# Sheet_Top_Front.net
KiCad netlist of a schematic drawn in Altium Designer
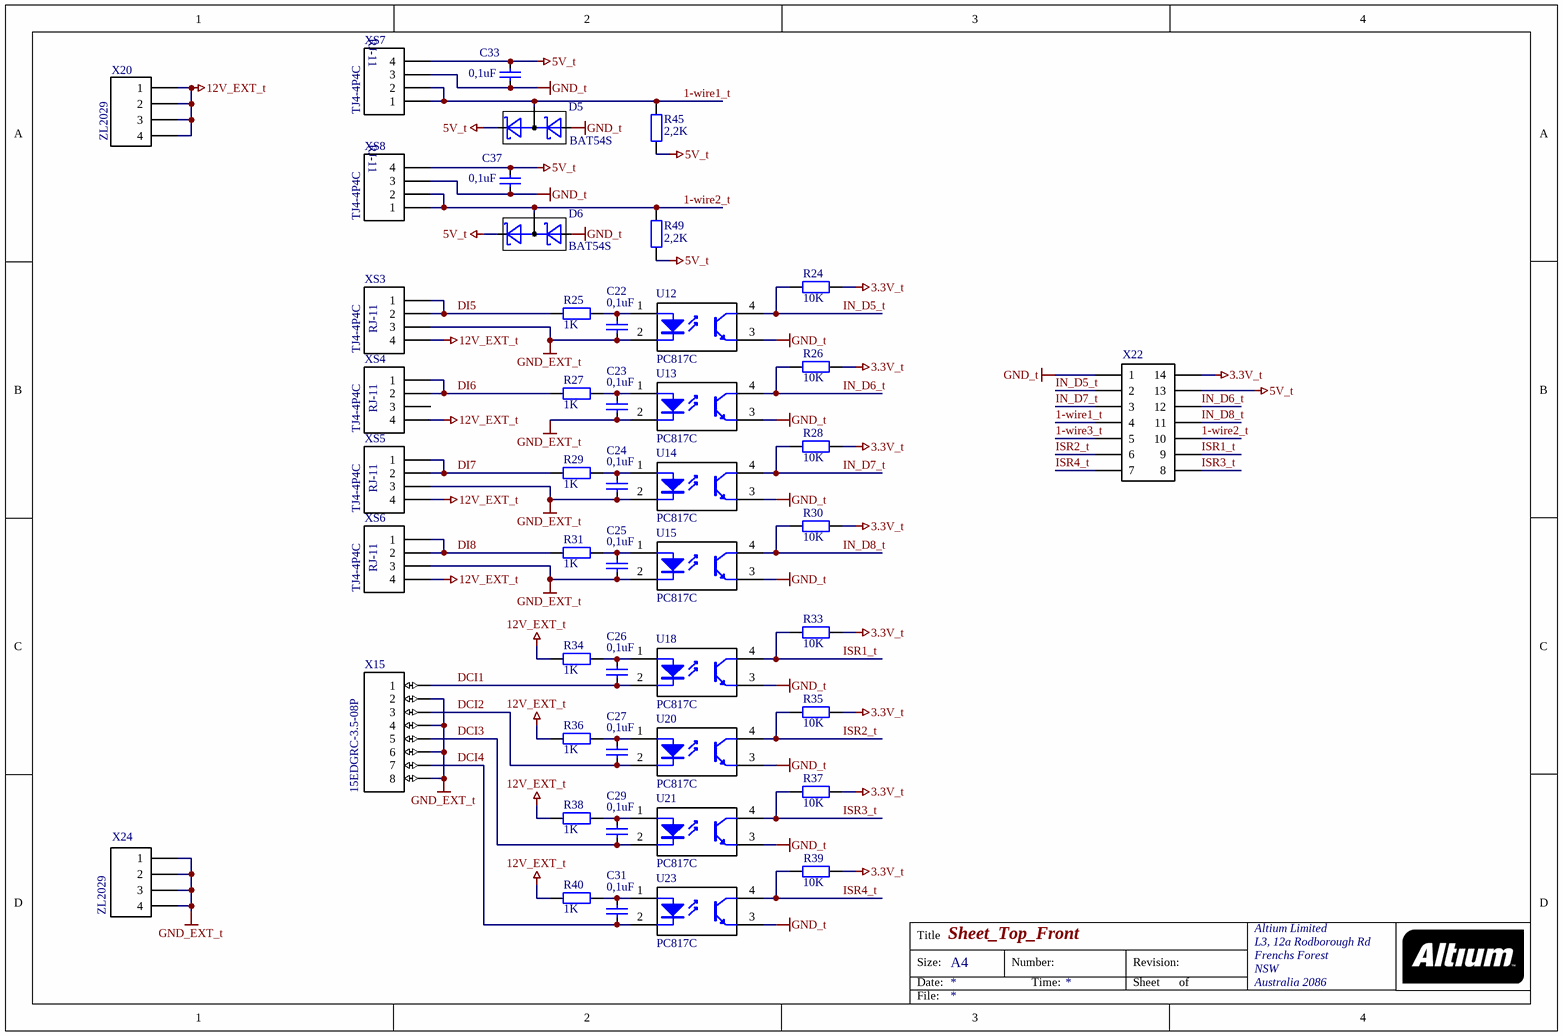
[diagram p0: Sheet_Top_Front.SchDoc]

(export (version "E")
  (design (tool "Eeschema 10.0.6"))
  (components
    (comp (ref "C22")
      (value "0,1uF")
      (footprint "C_0805")
      (description "Capacitor semi")
      (fields (field (name "Comment") "Cap_Semi"))
      (libsource (lib "Capacitor") (part "Cap_Semi"))
    )
    (comp (ref "C23")
      (value "0,1uF")
      (footprint "C_0805")
      (description "Capacitor semi")
      (fields (field (name "Comment") "Cap_Semi"))
      (libsource (lib "Capacitor") (part "Cap_Semi"))
    )
    (comp (ref "C24")
      (value "0,1uF")
      (footprint "C_0805")
      (description "Capacitor semi")
      (fields (field (name "Comment") "Cap_Semi"))
      (libsource (lib "Capacitor") (part "Cap_Semi"))
    )
    (comp (ref "C25")
      (value "0,1uF")
      (footprint "C_0805")
      (description "Capacitor semi")
      (fields (field (name "Comment") "Cap_Semi"))
      (libsource (lib "Capacitor") (part "Cap_Semi"))
    )
    (comp (ref "C26")
      (value "0,1uF")
      (footprint "C_0805")
      (description "Capacitor semi")
      (fields (field (name "Comment") "Cap_Semi"))
      (libsource (lib "Capacitor") (part "Cap_Semi"))
    )
    (comp (ref "C27")
      (value "0,1uF")
      (footprint "C_0805")
      (description "Capacitor semi")
      (fields (field (name "Comment") "Cap_Semi"))
      (libsource (lib "Capacitor") (part "Cap_Semi"))
    )
    (comp (ref "C29")
      (value "0,1uF")
      (footprint "C_0805")
      (description "Capacitor semi")
      (fields (field (name "Comment") "Cap_Semi"))
      (libsource (lib "Capacitor") (part "Cap_Semi"))
    )
    (comp (ref "C31")
      (value "0,1uF")
      (footprint "C_0805")
      (description "Capacitor semi")
      (fields (field (name "Comment") "Cap_Semi"))
      (libsource (lib "Capacitor") (part "Cap_Semi"))
    )
    (comp (ref "C33")
      (value "0,1uF")
      (footprint "C_0805")
      (description "Capacitor semi")
      (fields (field (name "Comment") "Cap_Semi"))
      (libsource (lib "Capacitor") (part "Cap_Semi"))
    )
    (comp (ref "C37")
      (value "0,1uF")
      (footprint "C_0805")
      (description "Capacitor semi")
      (fields (field (name "Comment") "Cap_Semi"))
      (libsource (lib "Capacitor") (part "Cap_Semi"))
    )
    (comp (ref "D5")
      (value "BAT54S")
      (footprint "SOT-23_d")
      (description "Diode Schottky")
      (libsource (lib "Diode") (part "BAT54S"))
    )
    (comp (ref "D6")
      (value "BAT54S")
      (footprint "SOT-23_d")
      (description "Diode Schottky")
      (libsource (lib "Diode") (part "BAT54S"))
    )
    (comp (ref "R24")
      (value "10K")
      (footprint "R_0805")
      (description "Resistor")
      (libsource (lib "Resistors") (part "Resistor"))
    )
    (comp (ref "R25")
      (value "1K")
      (footprint "R_0805")
      (description "Resistor")
      (libsource (lib "Resistors") (part "Resistor"))
    )
    (comp (ref "R26")
      (value "10K")
      (footprint "R_0805")
      (description "Resistor")
      (libsource (lib "Resistors") (part "Resistor"))
    )
    (comp (ref "R27")
      (value "1K")
      (footprint "R_0805")
      (description "Resistor")
      (libsource (lib "Resistors") (part "Resistor"))
    )
    (comp (ref "R28")
      (value "10K")
      (footprint "R_0805")
      (description "Resistor")
      (libsource (lib "Resistors") (part "Resistor"))
    )
    (comp (ref "R29")
      (value "1K")
      (footprint "R_0805")
      (description "Resistor")
      (libsource (lib "Resistors") (part "Resistor"))
    )
    (comp (ref "R30")
      (value "10K")
      (footprint "R_0805")
      (description "Resistor")
      (libsource (lib "Resistors") (part "Resistor"))
    )
    (comp (ref "R31")
      (value "1K")
      (footprint "R_0805")
      (description "Resistor")
      (libsource (lib "Resistors") (part "Resistor"))
    )
    (comp (ref "R33")
      (value "10K")
      (footprint "R_0805")
      (description "Resistor")
      (libsource (lib "Resistors") (part "Resistor"))
    )
    (comp (ref "R34")
      (value "1K")
      (footprint "R_0805")
      (description "Resistor")
      (libsource (lib "Resistors") (part "Resistor"))
    )
    (comp (ref "R35")
      (value "10K")
      (footprint "R_0805")
      (description "Resistor")
      (libsource (lib "Resistors") (part "Resistor"))
    )
    (comp (ref "R36")
      (value "1K")
      (footprint "R_0805")
      (description "Resistor")
      (libsource (lib "Resistors") (part "Resistor"))
    )
    (comp (ref "R37")
      (value "10K")
      (footprint "R_0805")
      (description "Resistor")
      (libsource (lib "Resistors") (part "Resistor"))
    )
    (comp (ref "R38")
      (value "1K")
      (footprint "R_0805")
      (description "Resistor")
      (libsource (lib "Resistors") (part "Resistor"))
    )
    (comp (ref "R39")
      (value "10K")
      (footprint "R_0805")
      (description "Resistor")
      (libsource (lib "Resistors") (part "Resistor"))
    )
    (comp (ref "R40")
      (value "1K")
      (footprint "R_0805")
      (description "Resistor")
      (libsource (lib "Resistors") (part "Resistor"))
    )
    (comp (ref "R45")
      (value "2,2K")
      (footprint "R_0805")
      (description "Resistor")
      (libsource (lib "Resistors") (part "Resistor"))
    )
    (comp (ref "R49")
      (value "2,2K")
      (footprint "R_0805")
      (description "Resistor")
      (libsource (lib "Resistors") (part "Resistor"))
    )
    (comp (ref "U12")
      (value "PC817C")
      (footprint "DIP-4")
      (description "Optocoupler")
      (libsource (lib "Chip_Packaging") (part "PC817"))
    )
    (comp (ref "U13")
      (value "PC817C")
      (footprint "DIP-4")
      (description "Optocoupler")
      (libsource (lib "Chip_Packaging") (part "PC817"))
    )
    (comp (ref "U14")
      (value "PC817C")
      (footprint "DIP-4")
      (description "Optocoupler")
      (libsource (lib "Chip_Packaging") (part "PC817"))
    )
    (comp (ref "U15")
      (value "PC817C")
      (footprint "DIP-4")
      (description "Optocoupler")
      (libsource (lib "Chip_Packaging") (part "PC817"))
    )
    (comp (ref "U18")
      (value "PC817C")
      (footprint "DIP-4")
      (description "Optocoupler")
      (libsource (lib "Chip_Packaging") (part "PC817"))
    )
    (comp (ref "U20")
      (value "PC817C")
      (footprint "DIP-4")
      (description "Optocoupler")
      (libsource (lib "Chip_Packaging") (part "PC817"))
    )
    (comp (ref "U21")
      (value "PC817C")
      (footprint "DIP-4")
      (description "Optocoupler")
      (libsource (lib "Chip_Packaging") (part "PC817"))
    )
    (comp (ref "U23")
      (value "PC817C")
      (footprint "DIP-4")
      (description "Optocoupler")
      (libsource (lib "Chip_Packaging") (part "PC817"))
    )
    (comp (ref "X15")
      (value "15EDGRC-3.5-08P")
      (footprint "MC_3.5_8")
      (description "Connector 3.5mm")
      (libsource (lib "Connect") (part "MC_3.5_8"))
    )
    (comp (ref "X20")
      (value "ZL2029")
      (footprint "PLS-4-3D")
      (description "Header, 4-Pin")
      (fields (field (name "ALTIUM_UNNAMED_1") "ZL2029") (field (name "PUBLISHER") "Altium Limited"))
      (libsource (lib "Connect") (part "PLS-4"))
    )
    (comp (ref "X22")
      (value "PLS2-14")
      (footprint "PLS2-14")
      (description "Header, 14-Pin")
      (libsource (lib "Connect") (part "PLS2-14"))
    )
    (comp (ref "X24")
      (value "PLS-4")
      (footprint "PLS-4-3D")
      (description "ZL2029")
      (fields (field (name "ALTIUM_UNNAMED_1") "ZL2029") (field (name "PUBLISHER") "Altium Limited"))
      (libsource (lib "Connect") (part "PLS-4"))
    )
    (comp (ref "XS3")
      (value "RJ-11")
      (footprint "RJ-11 - TJ4-4P4C")
      (description "TJ4-4P4C")
      (fields (field (name "ALTIUM_UNNAMED_1") "TJ4-4P4C"))
      (libsource (lib "Connect") (part "RJ-11"))
    )
    (comp (ref "XS4")
      (value "RJ-11")
      (footprint "RJ-11 - TJ4-4P4C")
      (description "TJ4-4P4C")
      (fields (field (name "ALTIUM_UNNAMED_1") "TJ4-4P4C"))
      (libsource (lib "Connect") (part "RJ-11"))
    )
    (comp (ref "XS5")
      (value "RJ-11")
      (footprint "RJ-11 - TJ4-4P4C")
      (description "TJ4-4P4C")
      (fields (field (name "ALTIUM_UNNAMED_1") "TJ4-4P4C"))
      (libsource (lib "Connect") (part "RJ-11"))
    )
    (comp (ref "XS6")
      (value "RJ-11")
      (footprint "RJ-11 - TJ4-4P4C")
      (description "TJ4-4P4C")
      (fields (field (name "ALTIUM_UNNAMED_1") "TJ4-4P4C"))
      (libsource (lib "Connect") (part "RJ-11"))
    )
    (comp (ref "XS7")
      (value "RJ-11")
      (footprint "RJ-11 - TJ4-4P4C")
      (description "TJ4-4P4C")
      (fields (field (name "ALTIUM_UNNAMED_1") "TJ4-4P4C"))
      (libsource (lib "") (part "RJ-11_1"))
    )
    (comp (ref "XS8")
      (value "RJ-11")
      (footprint "RJ-11 - TJ4-4P4C")
      (description "TJ4-4P4C")
      (fields (field (name "ALTIUM_UNNAMED_1") "TJ4-4P4C"))
      (libsource (lib "") (part "RJ-11_1"))
    )
  )
  (nets
    (net (code "1") (name "/1-wire1_t") (class "Default")
      (node (ref "D5") (pin "3") (pinfunction "CA_3") (pintype "passive"))
      (node (ref "R45") (pin "1") (pinfunction "1_1") (pintype "passive"))
      (node (ref "X22") (pin "4") (pinfunction "4_4") (pintype "passive"))
      (node (ref "XS7") (pin "1") (pinfunction "1_1") (pintype "passive"))
      (node (ref "XS7") (pin "2") (pinfunction "2_2") (pintype "passive"))
    )
    (net (code "2") (name "/1-wire2_t") (class "Default")
      (node (ref "D6") (pin "3") (pinfunction "CA_3") (pintype "passive"))
      (node (ref "R49") (pin "1") (pinfunction "1_1") (pintype "passive"))
      (node (ref "X22") (pin "10") (pinfunction "10_10") (pintype "passive"))
      (node (ref "XS8") (pin "1") (pinfunction "1_1") (pintype "passive"))
      (node (ref "XS8") (pin "2") (pinfunction "2_2") (pintype "passive"))
    )
    (net (code "3") (name "/1-wire3_t") (class "Default")
      (node (ref "X22") (pin "5") (pinfunction "5_5") (pintype "passive"))
    )
    (net (code "4") (name "/DCI1") (class "Default")
      (node (ref "C26") (pin "2") (pinfunction "2_2") (pintype "passive"))
      (node (ref "U18") (pin "2") (pinfunction "K_2") (pintype "passive"))
      (node (ref "X15") (pin "1") (pinfunction "1_1") (pintype "bidirectional"))
    )
    (net (code "5") (name "/DCI2") (class "Default")
      (node (ref "C27") (pin "2") (pinfunction "2_2") (pintype "passive"))
      (node (ref "U20") (pin "2") (pinfunction "K_2") (pintype "passive"))
      (node (ref "X15") (pin "3") (pinfunction "3_3") (pintype "bidirectional"))
    )
    (net (code "6") (name "/DCI3") (class "Default")
      (node (ref "C29") (pin "2") (pinfunction "2_2") (pintype "passive"))
      (node (ref "U21") (pin "2") (pinfunction "K_2") (pintype "passive"))
      (node (ref "X15") (pin "5") (pinfunction "5_5") (pintype "bidirectional"))
    )
    (net (code "7") (name "/DCI4") (class "Default")
      (node (ref "C31") (pin "2") (pinfunction "2_2") (pintype "passive"))
      (node (ref "U23") (pin "2") (pinfunction "K_2") (pintype "passive"))
      (node (ref "X15") (pin "7") (pinfunction "7_7") (pintype "bidirectional"))
    )
    (net (code "8") (name "/DI5") (class "Default")
      (node (ref "R25") (pin "2") (pinfunction "2_2") (pintype "passive"))
      (node (ref "XS3") (pin "1") (pinfunction "1_1") (pintype "passive"))
      (node (ref "XS3") (pin "2") (pinfunction "2_2") (pintype "passive"))
    )
    (net (code "9") (name "/DI6") (class "Default")
      (node (ref "R27") (pin "2") (pinfunction "2_2") (pintype "passive"))
      (node (ref "XS4") (pin "1") (pinfunction "1_1") (pintype "passive"))
      (node (ref "XS4") (pin "2") (pinfunction "2_2") (pintype "passive"))
    )
    (net (code "10") (name "/DI7") (class "Default")
      (node (ref "R29") (pin "2") (pinfunction "2_2") (pintype "passive"))
      (node (ref "XS5") (pin "1") (pinfunction "1_1") (pintype "passive"))
      (node (ref "XS5") (pin "2") (pinfunction "2_2") (pintype "passive"))
    )
    (net (code "11") (name "/DI8") (class "Default")
      (node (ref "R31") (pin "2") (pinfunction "2_2") (pintype "passive"))
      (node (ref "XS6") (pin "1") (pinfunction "1_1") (pintype "passive"))
      (node (ref "XS6") (pin "2") (pinfunction "2_2") (pintype "passive"))
    )
    (net (code "12") (name "/IN_D5_t") (class "Default")
      (node (ref "R24") (pin "2") (pinfunction "2_2") (pintype "passive"))
      (node (ref "U12") (pin "4") (pinfunction "C_4") (pintype "passive"))
      (node (ref "X22") (pin "2") (pinfunction "2_2") (pintype "passive"))
    )
    (net (code "13") (name "/IN_D6_t") (class "Default")
      (node (ref "R26") (pin "2") (pinfunction "2_2") (pintype "passive"))
      (node (ref "U13") (pin "4") (pinfunction "C_4") (pintype "passive"))
      (node (ref "X22") (pin "12") (pinfunction "12_12") (pintype "passive"))
    )
    (net (code "14") (name "/IN_D7_t") (class "Default")
      (node (ref "R28") (pin "2") (pinfunction "2_2") (pintype "passive"))
      (node (ref "U14") (pin "4") (pinfunction "C_4") (pintype "passive"))
      (node (ref "X22") (pin "3") (pinfunction "3_3") (pintype "passive"))
    )
    (net (code "15") (name "/IN_D8_t") (class "Default")
      (node (ref "R30") (pin "2") (pinfunction "2_2") (pintype "passive"))
      (node (ref "U15") (pin "4") (pinfunction "C_4") (pintype "passive"))
      (node (ref "X22") (pin "11") (pinfunction "11_11") (pintype "passive"))
    )
    (net (code "16") (name "/ISR1_t") (class "Default")
      (node (ref "R33") (pin "2") (pinfunction "2_2") (pintype "passive"))
      (node (ref "U18") (pin "4") (pinfunction "C_4") (pintype "passive"))
      (node (ref "X22") (pin "9") (pinfunction "9_9") (pintype "passive"))
    )
    (net (code "17") (name "/ISR2_t") (class "Default")
      (node (ref "R35") (pin "2") (pinfunction "2_2") (pintype "passive"))
      (node (ref "U20") (pin "4") (pinfunction "C_4") (pintype "passive"))
      (node (ref "X22") (pin "6") (pinfunction "6_6") (pintype "passive"))
    )
    (net (code "18") (name "/ISR3_t") (class "Default")
      (node (ref "R37") (pin "2") (pinfunction "2_2") (pintype "passive"))
      (node (ref "U21") (pin "4") (pinfunction "C_4") (pintype "passive"))
      (node (ref "X22") (pin "8") (pinfunction "8_8") (pintype "passive"))
    )
    (net (code "19") (name "/ISR4_t") (class "Default")
      (node (ref "R39") (pin "2") (pinfunction "2_2") (pintype "passive"))
      (node (ref "U23") (pin "4") (pinfunction "C_4") (pintype "passive"))
      (node (ref "X22") (pin "7") (pinfunction "7_7") (pintype "passive"))
    )
    (net (code "20") (name "3.3V_t") (class "Default")
      (node (ref "R24") (pin "1") (pinfunction "1_1") (pintype "passive"))
      (node (ref "R26") (pin "1") (pinfunction "1_1") (pintype "passive"))
      (node (ref "R28") (pin "1") (pinfunction "1_1") (pintype "passive"))
      (node (ref "R30") (pin "1") (pinfunction "1_1") (pintype "passive"))
      (node (ref "R33") (pin "1") (pinfunction "1_1") (pintype "passive"))
      (node (ref "R35") (pin "1") (pinfunction "1_1") (pintype "passive"))
      (node (ref "R37") (pin "1") (pinfunction "1_1") (pintype "passive"))
      (node (ref "R39") (pin "1") (pinfunction "1_1") (pintype "passive"))
      (node (ref "X22") (pin "14") (pinfunction "14_14") (pintype "passive"))
    )
    (net (code "21") (name "5V_t") (class "Default")
      (node (ref "C33") (pin "1") (pinfunction "1_1") (pintype "passive"))
      (node (ref "C37") (pin "1") (pinfunction "1_1") (pintype "passive"))
      (node (ref "D5") (pin "2") (pinfunction "C_2") (pintype "passive"))
      (node (ref "D6") (pin "2") (pinfunction "C_2") (pintype "passive"))
      (node (ref "R45") (pin "2") (pinfunction "2_2") (pintype "passive"))
      (node (ref "R49") (pin "2") (pinfunction "2_2") (pintype "passive"))
      (node (ref "X22") (pin "13") (pinfunction "13_13") (pintype "passive"))
      (node (ref "XS7") (pin "4") (pinfunction "4_4") (pintype "passive"))
      (node (ref "XS8") (pin "4") (pinfunction "4_4") (pintype "passive"))
    )
    (net (code "22") (name "12V_EXT_t") (class "Default")
      (node (ref "R34") (pin "2") (pinfunction "2_2") (pintype "passive"))
      (node (ref "R36") (pin "2") (pinfunction "2_2") (pintype "passive"))
      (node (ref "R38") (pin "2") (pinfunction "2_2") (pintype "passive"))
      (node (ref "R40") (pin "2") (pinfunction "2_2") (pintype "passive"))
      (node (ref "X20") (pin "1") (pinfunction "1_1") (pintype "passive"))
      (node (ref "X20") (pin "2") (pinfunction "2_2") (pintype "passive"))
      (node (ref "X20") (pin "3") (pinfunction "3_3") (pintype "passive"))
      (node (ref "X20") (pin "4") (pinfunction "4_4") (pintype "passive"))
      (node (ref "XS3") (pin "4") (pinfunction "4_4") (pintype "passive"))
      (node (ref "XS4") (pin "4") (pinfunction "4_4") (pintype "passive"))
      (node (ref "XS5") (pin "4") (pinfunction "4_4") (pintype "passive"))
      (node (ref "XS6") (pin "4") (pinfunction "4_4") (pintype "passive"))
    )
    (net (code "23") (name "GND_EXT_t") (class "Default")
      (node (ref "C22") (pin "2") (pinfunction "2_2") (pintype "passive"))
      (node (ref "C23") (pin "2") (pinfunction "2_2") (pintype "passive"))
      (node (ref "C24") (pin "2") (pinfunction "2_2") (pintype "passive"))
      (node (ref "C25") (pin "2") (pinfunction "2_2") (pintype "passive"))
      (node (ref "U12") (pin "2") (pinfunction "K_2") (pintype "passive"))
      (node (ref "U13") (pin "2") (pinfunction "K_2") (pintype "passive"))
      (node (ref "U14") (pin "2") (pinfunction "K_2") (pintype "passive"))
      (node (ref "U15") (pin "2") (pinfunction "K_2") (pintype "passive"))
      (node (ref "X15") (pin "2") (pinfunction "2_2") (pintype "bidirectional"))
      (node (ref "X15") (pin "4") (pinfunction "4_4") (pintype "bidirectional"))
      (node (ref "X15") (pin "6") (pinfunction "6_6") (pintype "bidirectional"))
      (node (ref "X15") (pin "8") (pinfunction "8_8") (pintype "bidirectional"))
      (node (ref "X24") (pin "1") (pinfunction "1_1") (pintype "passive"))
      (node (ref "X24") (pin "2") (pinfunction "2_2") (pintype "passive"))
      (node (ref "X24") (pin "3") (pinfunction "3_3") (pintype "passive"))
      (node (ref "X24") (pin "4") (pinfunction "4_4") (pintype "passive"))
      (node (ref "XS3") (pin "3") (pinfunction "3_3") (pintype "passive"))
      (node (ref "XS5") (pin "3") (pinfunction "3_3") (pintype "passive"))
      (node (ref "XS6") (pin "3") (pinfunction "3_3") (pintype "passive"))
    )
    (net (code "24") (name "GND_t") (class "Default")
      (node (ref "C33") (pin "2") (pinfunction "2_2") (pintype "passive"))
      (node (ref "C37") (pin "2") (pinfunction "2_2") (pintype "passive"))
      (node (ref "D5") (pin "1") (pinfunction "A_1") (pintype "passive"))
      (node (ref "D6") (pin "1") (pinfunction "A_1") (pintype "passive"))
      (node (ref "U12") (pin "3") (pinfunction "E_3") (pintype "passive"))
      (node (ref "U13") (pin "3") (pinfunction "E_3") (pintype "passive"))
      (node (ref "U14") (pin "3") (pinfunction "E_3") (pintype "passive"))
      (node (ref "U15") (pin "3") (pinfunction "E_3") (pintype "passive"))
      (node (ref "U18") (pin "3") (pinfunction "E_3") (pintype "passive"))
      (node (ref "U20") (pin "3") (pinfunction "E_3") (pintype "passive"))
      (node (ref "U21") (pin "3") (pinfunction "E_3") (pintype "passive"))
      (node (ref "U23") (pin "3") (pinfunction "E_3") (pintype "passive"))
      (node (ref "X22") (pin "1") (pinfunction "1_1") (pintype "passive"))
      (node (ref "XS7") (pin "3") (pinfunction "3_3") (pintype "passive"))
      (node (ref "XS8") (pin "3") (pinfunction "3_3") (pintype "passive"))
    )
    (net (code "25") (name "Net-(U12-A)") (class "Default")
      (node (ref "C22") (pin "1") (pinfunction "1_1") (pintype "passive"))
      (node (ref "R25") (pin "1") (pinfunction "1_1") (pintype "passive"))
      (node (ref "U12") (pin "1") (pinfunction "A_1") (pintype "passive"))
    )
    (net (code "26") (name "Net-(U13-A)") (class "Default")
      (node (ref "C23") (pin "1") (pinfunction "1_1") (pintype "passive"))
      (node (ref "R27") (pin "1") (pinfunction "1_1") (pintype "passive"))
      (node (ref "U13") (pin "1") (pinfunction "A_1") (pintype "passive"))
    )
    (net (code "27") (name "Net-(U14-A)") (class "Default")
      (node (ref "C24") (pin "1") (pinfunction "1_1") (pintype "passive"))
      (node (ref "R29") (pin "1") (pinfunction "1_1") (pintype "passive"))
      (node (ref "U14") (pin "1") (pinfunction "A_1") (pintype "passive"))
    )
    (net (code "28") (name "Net-(U15-A)") (class "Default")
      (node (ref "C25") (pin "1") (pinfunction "1_1") (pintype "passive"))
      (node (ref "R31") (pin "1") (pinfunction "1_1") (pintype "passive"))
      (node (ref "U15") (pin "1") (pinfunction "A_1") (pintype "passive"))
    )
    (net (code "29") (name "Net-(U18-A)") (class "Default")
      (node (ref "C26") (pin "1") (pinfunction "1_1") (pintype "passive"))
      (node (ref "R34") (pin "1") (pinfunction "1_1") (pintype "passive"))
      (node (ref "U18") (pin "1") (pinfunction "A_1") (pintype "passive"))
    )
    (net (code "30") (name "Net-(U20-A)") (class "Default")
      (node (ref "C27") (pin "1") (pinfunction "1_1") (pintype "passive"))
      (node (ref "R36") (pin "1") (pinfunction "1_1") (pintype "passive"))
      (node (ref "U20") (pin "1") (pinfunction "A_1") (pintype "passive"))
    )
    (net (code "31") (name "Net-(U21-A)") (class "Default")
      (node (ref "C29") (pin "1") (pinfunction "1_1") (pintype "passive"))
      (node (ref "R38") (pin "1") (pinfunction "1_1") (pintype "passive"))
      (node (ref "U21") (pin "1") (pinfunction "A_1") (pintype "passive"))
    )
    (net (code "32") (name "Net-(U23-A)") (class "Default")
      (node (ref "C31") (pin "1") (pinfunction "1_1") (pintype "passive"))
      (node (ref "R40") (pin "1") (pinfunction "1_1") (pintype "passive"))
      (node (ref "U23") (pin "1") (pinfunction "A_1") (pintype "passive"))
    )
    (net (code "33") (name "unconnected-(XS4-Pad3)") (class "Default")
      (node (ref "XS4") (pin "3") (pinfunction "3_3") (pintype "passive"))
    )
  )
)
